# Filter.net
KiCad netlist of a schematic drawn in Altium Designer
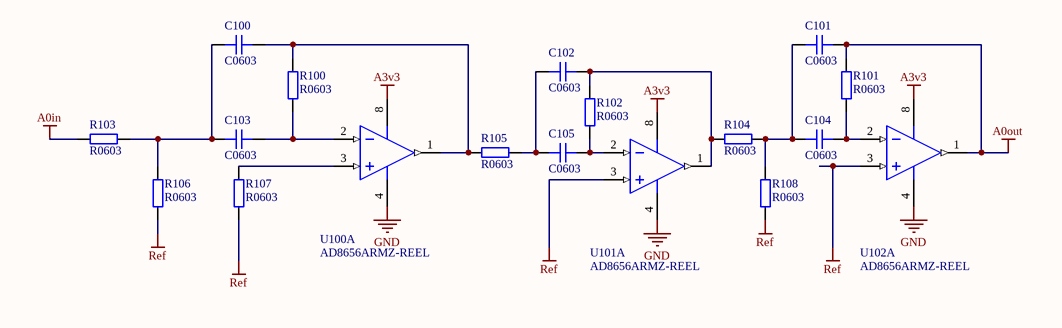
[diagram p0: Filter.SchDoc]

(export (version "E")
  (design (tool "Eeschema 10.0.6"))
  (components
    (comp (ref "C100")
      (value "C0603")
      (footprint "CAP_0603")
      (description "Capacitor SMD 0603")
      (libsource (lib "Schematic-Lib-PhilsLab") (part "CAP_0603"))
    )
    (comp (ref "C101")
      (value "C0603")
      (footprint "CAP_0603")
      (description "Capacitor SMD 0603")
      (libsource (lib "Schematic-Lib-PhilsLab") (part "CAP_0603"))
    )
    (comp (ref "C102")
      (value "C0603")
      (footprint "CAP_0603")
      (description "Capacitor SMD 0603")
      (libsource (lib "Schematic-Lib-PhilsLab") (part "CAP_0603"))
    )
    (comp (ref "C103")
      (value "C0603")
      (footprint "CAP_0603")
      (description "Capacitor SMD 0603")
      (libsource (lib "Schematic-Lib-PhilsLab") (part "CAP_0603"))
    )
    (comp (ref "C104")
      (value "C0603")
      (footprint "CAP_0603")
      (description "Capacitor SMD 0603")
      (libsource (lib "Schematic-Lib-PhilsLab") (part "CAP_0603"))
    )
    (comp (ref "C105")
      (value "C0603")
      (footprint "CAP_0603")
      (description "Capacitor SMD 0603")
      (libsource (lib "Schematic-Lib-PhilsLab") (part "CAP_0603"))
    )
    (comp (ref "R100")
      (value "R0603")
      (footprint "RES_0603")
      (description "Resistor SMD 0603")
      (libsource (lib "Schematic-Lib-PhilsLab") (part "RES_0603"))
    )
    (comp (ref "R101")
      (value "R0603")
      (footprint "RES_0603")
      (description "Resistor SMD 0603")
      (libsource (lib "Schematic-Lib-PhilsLab") (part "RES_0603"))
    )
    (comp (ref "R102")
      (value "R0603")
      (footprint "RES_0603")
      (description "Resistor SMD 0603")
      (libsource (lib "Schematic-Lib-PhilsLab") (part "RES_0603"))
    )
    (comp (ref "R103")
      (value "R0603")
      (footprint "RES_0603")
      (description "Resistor SMD 0603")
      (libsource (lib "Schematic-Lib-PhilsLab") (part "RES_0603"))
    )
    (comp (ref "R104")
      (value "R0603")
      (footprint "RES_0603")
      (description "Resistor SMD 0603")
      (libsource (lib "Schematic-Lib-PhilsLab") (part "RES_0603"))
    )
    (comp (ref "R105")
      (value "R0603")
      (footprint "RES_0603")
      (description "Resistor SMD 0603")
      (libsource (lib "Schematic-Lib-PhilsLab") (part "RES_0603"))
    )
    (comp (ref "R106")
      (value "R0603")
      (footprint "RES_0603")
      (description "Resistor SMD 0603")
      (libsource (lib "Schematic-Lib-PhilsLab") (part "RES_0603"))
    )
    (comp (ref "R107")
      (value "R0603")
      (footprint "RES_0603")
      (description "Resistor SMD 0603")
      (libsource (lib "Schematic-Lib-PhilsLab") (part "RES_0603"))
    )
    (comp (ref "R108")
      (value "R0603")
      (footprint "RES_0603")
      (description "Resistor SMD 0603")
      (libsource (lib "Schematic-Lib-PhilsLab") (part "RES_0603"))
    )
    (comp (ref "U100")
      (value "AD8656ARMZ-REEL")
      (footprint "ADI-RM-8_N")
      (fields (field (name "GENERIC PART NUMBER") "AD8656") (field (name "MANUFACTURER") "Analog Devices"))
      (libsource (lib "Altium Content Vault") (part "ADI-OP29X-R-8"))
    )
    (comp (ref "U101")
      (value "AD8656ARMZ-REEL")
      (footprint "ADI-RM-8_N")
      (fields (field (name "GENERIC PART NUMBER") "AD8656") (field (name "MANUFACTURER") "Analog Devices"))
      (libsource (lib "Altium Content Vault") (part "ADI-OP29X-R-8"))
    )
    (comp (ref "U102")
      (value "AD8656ARMZ-REEL")
      (footprint "ADI-RM-8_N")
      (fields (field (name "GENERIC PART NUMBER") "AD8656") (field (name "MANUFACTURER") "Analog Devices"))
      (libsource (lib "Altium Content Vault") (part "ADI-OP29X-R-8"))
    )
  )
  (nets
    (net (code "1") (name "A0in") (class "Default")
      (node (ref "R103") (pin "2") (pinfunction "2_2") (pintype "passive"))
    )
    (net (code "2") (name "A0out") (class "Default")
      (node (ref "C101") (pin "2") (pinfunction "2_2") (pintype "passive"))
      (node (ref "R101") (pin "2") (pinfunction "2_2") (pintype "passive"))
      (node (ref "U102") (pin "1") (pinfunction "OUT_A_1") (pintype "output"))
    )
    (net (code "3") (name "A3v3") (class "Default")
      (node (ref "U100") (pin "8") (pinfunction "+V_8") (pintype "power_in"))
      (node (ref "U101") (pin "8") (pinfunction "+V_8") (pintype "power_in"))
      (node (ref "U102") (pin "8") (pinfunction "+V_8") (pintype "power_in"))
    )
    (net (code "4") (name "GND") (class "Default")
      (node (ref "U100") (pin "4") (pinfunction "-V_4") (pintype "power_in"))
      (node (ref "U101") (pin "4") (pinfunction "-V_4") (pintype "power_in"))
      (node (ref "U102") (pin "4") (pinfunction "-V_4") (pintype "power_in"))
    )
    (net (code "5") (name "Net-(C100-Pad1)") (class "Default")
      (node (ref "C100") (pin "1") (pinfunction "1_1") (pintype "passive"))
      (node (ref "C103") (pin "1") (pinfunction "1_1") (pintype "passive"))
      (node (ref "R103") (pin "1") (pinfunction "1_1") (pintype "passive"))
      (node (ref "R106") (pin "1") (pinfunction "1_1") (pintype "passive"))
    )
    (net (code "6") (name "Net-(C101-Pad1)") (class "Default")
      (node (ref "C101") (pin "1") (pinfunction "1_1") (pintype "passive"))
      (node (ref "C104") (pin "1") (pinfunction "1_1") (pintype "passive"))
      (node (ref "R104") (pin "1") (pinfunction "1_1") (pintype "passive"))
      (node (ref "R108") (pin "2") (pinfunction "2_2") (pintype "passive"))
    )
    (net (code "7") (name "Net-(C102-Pad1)") (class "Default")
      (node (ref "C102") (pin "1") (pinfunction "1_1") (pintype "passive"))
      (node (ref "C105") (pin "1") (pinfunction "1_1") (pintype "passive"))
      (node (ref "R105") (pin "1") (pinfunction "1_1") (pintype "passive"))
    )
    (net (code "8") (name "Net-(U100A-+IN_A)") (class "Default")
      (node (ref "R107") (pin "2") (pinfunction "2_2") (pintype "passive"))
      (node (ref "U100") (pin "3") (pinfunction "+IN_A_3") (pintype "input"))
    )
    (net (code "9") (name "Net-(U100A--IN_A)") (class "Default")
      (node (ref "C103") (pin "2") (pinfunction "2_2") (pintype "passive"))
      (node (ref "R100") (pin "1") (pinfunction "1_1") (pintype "passive"))
      (node (ref "U100") (pin "2") (pinfunction "-IN_A_2") (pintype "input"))
    )
    (net (code "10") (name "Net-(U100A-OUT_A)") (class "Default")
      (node (ref "C100") (pin "2") (pinfunction "2_2") (pintype "passive"))
      (node (ref "R100") (pin "2") (pinfunction "2_2") (pintype "passive"))
      (node (ref "R105") (pin "2") (pinfunction "2_2") (pintype "passive"))
      (node (ref "U100") (pin "1") (pinfunction "OUT_A_1") (pintype "output"))
    )
    (net (code "11") (name "Net-(U101A--IN_A)") (class "Default")
      (node (ref "C105") (pin "2") (pinfunction "2_2") (pintype "passive"))
      (node (ref "R102") (pin "1") (pinfunction "1_1") (pintype "passive"))
      (node (ref "U101") (pin "2") (pinfunction "-IN_A_2") (pintype "input"))
    )
    (net (code "12") (name "Net-(U101A-OUT_A)") (class "Default")
      (node (ref "C102") (pin "2") (pinfunction "2_2") (pintype "passive"))
      (node (ref "R102") (pin "2") (pinfunction "2_2") (pintype "passive"))
      (node (ref "R104") (pin "2") (pinfunction "2_2") (pintype "passive"))
      (node (ref "U101") (pin "1") (pinfunction "OUT_A_1") (pintype "output"))
    )
    (net (code "13") (name "Net-(U102A--IN_A)") (class "Default")
      (node (ref "C104") (pin "2") (pinfunction "2_2") (pintype "passive"))
      (node (ref "R101") (pin "1") (pinfunction "1_1") (pintype "passive"))
      (node (ref "U102") (pin "2") (pinfunction "-IN_A_2") (pintype "input"))
    )
    (net (code "14") (name "Ref") (class "Default")
      (node (ref "R106") (pin "2") (pinfunction "2_2") (pintype "passive"))
      (node (ref "R107") (pin "1") (pinfunction "1_1") (pintype "passive"))
      (node (ref "R108") (pin "1") (pinfunction "1_1") (pintype "passive"))
      (node (ref "U101") (pin "3") (pinfunction "+IN_A_3") (pintype "input"))
      (node (ref "U102") (pin "3") (pinfunction "+IN_A_3") (pintype "input"))
    )
  )
)
